# DIYTIL311_v0.net
KiCad netlist of a schematic drawn in EAGLE
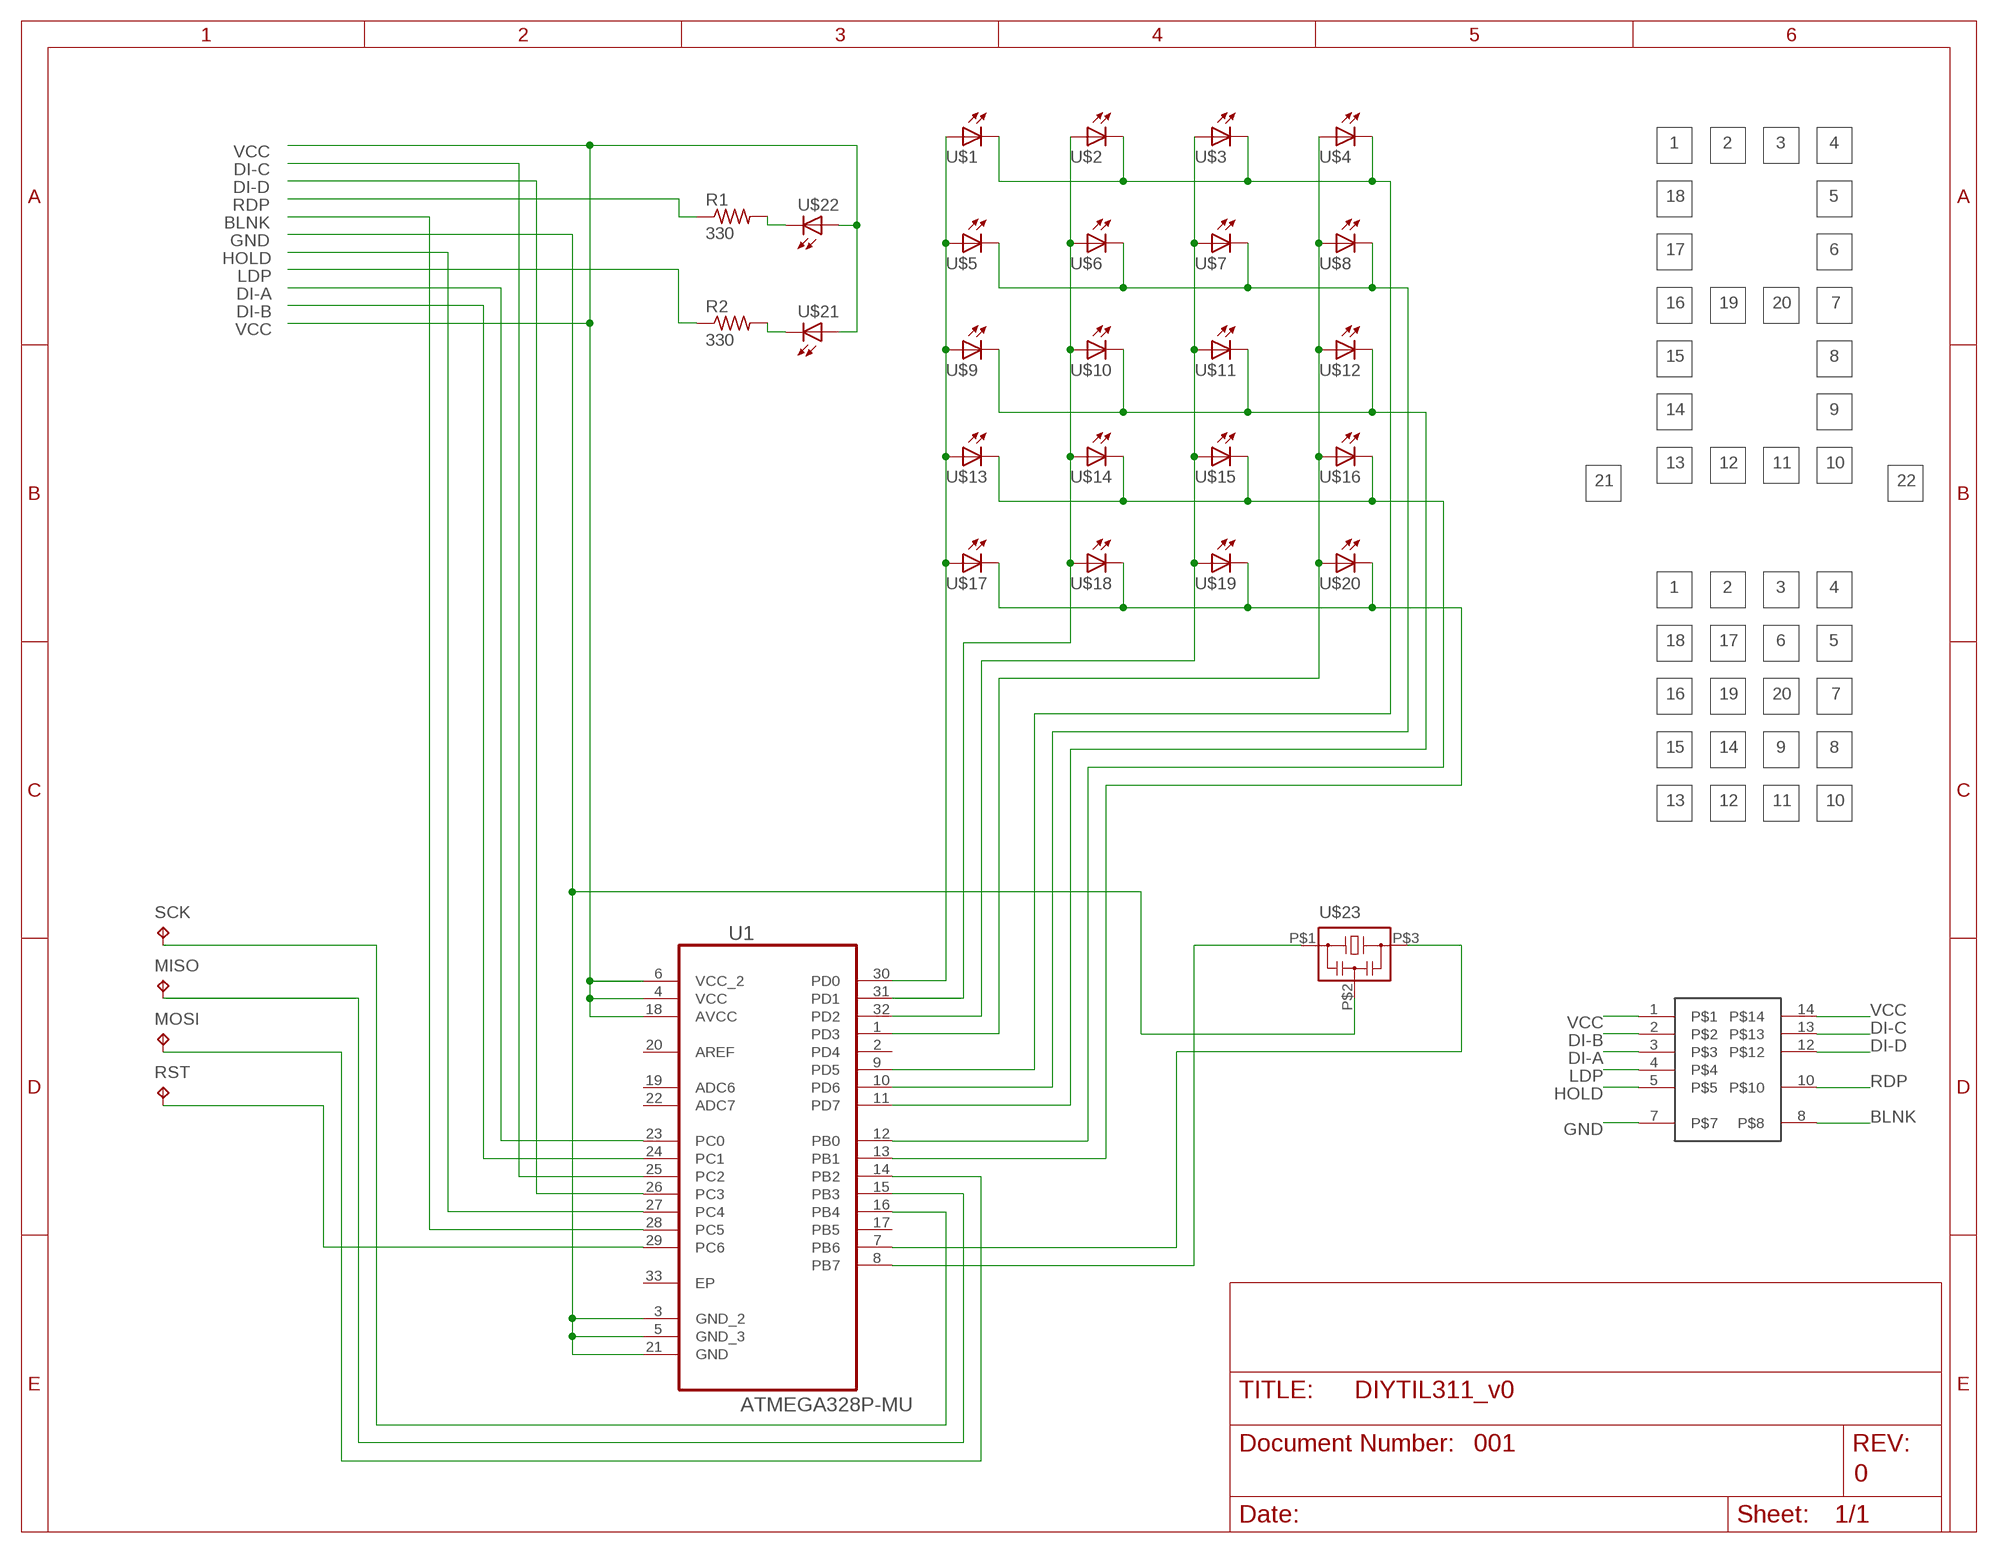
[diagram p0: schematic, sheet 1]

(export (version "E")
  (design (tool "Eeschema 10.0.6"))
  (components
    (comp (ref "MISO")
      (value "TPB1,27")
      (footprint "eagle-import:B1,27")
      (libsource (lib "eagle-import") (part "TPB1,27"))
    )
    (comp (ref "MOSI")
      (value "TPB1,27")
      (footprint "eagle-import:B1,27")
      (libsource (lib "eagle-import") (part "TPB1,27"))
    )
    (comp (ref "R1")
      (value "330")
      (footprint "eagle-import:R0201")
      (libsource (lib "eagle-import") (part "R-US_R0201"))
    )
    (comp (ref "R2")
      (value "330")
      (footprint "eagle-import:R0201")
      (libsource (lib "eagle-import") (part "R-US_R0201"))
    )
    (comp (ref "RST")
      (value "TPB1,27")
      (footprint "eagle-import:B1,27")
      (libsource (lib "eagle-import") (part "TPB1,27"))
    )
    (comp (ref "SCK")
      (value "TPB1,27")
      (footprint "eagle-import:B1,27")
      (libsource (lib "eagle-import") (part "TPB1,27"))
    )
    (comp (ref "U$1")
      (value "0201.LED0201")
      (footprint "eagle-import:LEDC0603X33")
      (libsource (lib "eagle-import") (part "0201.LED0201"))
    )
    (comp (ref "U$2")
      (value "0201.LED0201")
      (footprint "eagle-import:LEDC0603X33")
      (libsource (lib "eagle-import") (part "0201.LED0201"))
    )
    (comp (ref "U$3")
      (value "0201.LED0201")
      (footprint "eagle-import:LEDC0603X33")
      (libsource (lib "eagle-import") (part "0201.LED0201"))
    )
    (comp (ref "U$4")
      (value "0201.LED0201")
      (footprint "eagle-import:LEDC0603X33")
      (libsource (lib "eagle-import") (part "0201.LED0201"))
    )
    (comp (ref "U$5")
      (value "0201.LED0201")
      (footprint "eagle-import:LEDC0603X33")
      (libsource (lib "eagle-import") (part "0201.LED0201"))
    )
    (comp (ref "U$6")
      (value "0201.LED0201")
      (footprint "eagle-import:LEDC0603X33")
      (libsource (lib "eagle-import") (part "0201.LED0201"))
    )
    (comp (ref "U$7")
      (value "0201.LED0201")
      (footprint "eagle-import:LEDC0603X33")
      (libsource (lib "eagle-import") (part "0201.LED0201"))
    )
    (comp (ref "U$8")
      (value "0201.LED0201")
      (footprint "eagle-import:LEDC0603X33")
      (libsource (lib "eagle-import") (part "0201.LED0201"))
    )
    (comp (ref "U$9")
      (value "0201.LED0201")
      (footprint "eagle-import:LEDC0603X33")
      (libsource (lib "eagle-import") (part "0201.LED0201"))
    )
    (comp (ref "U$10")
      (value "0201.LED0201")
      (footprint "eagle-import:LEDC0603X33")
      (libsource (lib "eagle-import") (part "0201.LED0201"))
    )
    (comp (ref "U$11")
      (value "0201.LED0201")
      (footprint "eagle-import:LEDC0603X33")
      (libsource (lib "eagle-import") (part "0201.LED0201"))
    )
    (comp (ref "U$12")
      (value "0201.LED0201")
      (footprint "eagle-import:LEDC0603X33")
      (libsource (lib "eagle-import") (part "0201.LED0201"))
    )
    (comp (ref "U$13")
      (value "0201.LED0201")
      (footprint "eagle-import:LEDC0603X33")
      (libsource (lib "eagle-import") (part "0201.LED0201"))
    )
    (comp (ref "U$14")
      (value "0201.LED0201")
      (footprint "eagle-import:LEDC0603X33")
      (libsource (lib "eagle-import") (part "0201.LED0201"))
    )
    (comp (ref "U$15")
      (value "0201.LED0201")
      (footprint "eagle-import:LEDC0603X33")
      (libsource (lib "eagle-import") (part "0201.LED0201"))
    )
    (comp (ref "U$16")
      (value "0201.LED0201")
      (footprint "eagle-import:LEDC0603X33")
      (libsource (lib "eagle-import") (part "0201.LED0201"))
    )
    (comp (ref "U$17")
      (value "0201.LED0201")
      (footprint "eagle-import:LEDC0603X33")
      (libsource (lib "eagle-import") (part "0201.LED0201"))
    )
    (comp (ref "U$18")
      (value "0201.LED0201")
      (footprint "eagle-import:LEDC0603X33")
      (libsource (lib "eagle-import") (part "0201.LED0201"))
    )
    (comp (ref "U$19")
      (value "0201.LED0201")
      (footprint "eagle-import:LEDC0603X33")
      (libsource (lib "eagle-import") (part "0201.LED0201"))
    )
    (comp (ref "U$20")
      (value "0201.LED0201")
      (footprint "eagle-import:LEDC0603X33")
      (libsource (lib "eagle-import") (part "0201.LED0201"))
    )
    (comp (ref "U$21")
      (value "0201.LED0201")
      (footprint "eagle-import:LEDC0603X33")
      (libsource (lib "eagle-import") (part "0201.LED0201"))
    )
    (comp (ref "U$22")
      (value "0201.LED0201")
      (footprint "eagle-import:LEDC0603X33")
      (libsource (lib "eagle-import") (part "0201.LED0201"))
    )
    (comp (ref "U$23")
      (value "CSTNE16M0V53Z000R0")
      (footprint "eagle-import:MFF")
      (libsource (lib "eagle-import") (part "CSTNE16M0V53Z000R0"))
    )
    (comp (ref "U$24")
      (value "TIL311DIP")
      (footprint "eagle-import:TIL311DIP_FOOTPRINT")
      (libsource (lib "eagle-import") (part "TIL311DIP"))
    )
    (comp (ref "U1")
      (value "ATMEGA328P-MU")
      (footprint "eagle-import:QFN50P500X500X100-33N")
      (libsource (lib "eagle-import") (part "ATMEGA328P-MU"))
    )
  )
  (nets
    (net (code "1") (name "/BLNK") (class "Default")
      (node (ref "U$24") (pin "8") (pinfunction "P$8_8") (pintype "bidirectional"))
      (node (ref "U1") (pin "28") (pinfunction "PC5_28") (pintype "bidirectional"))
    )
    (net (code "2") (name "/DI-A") (class "Default")
      (node (ref "U$24") (pin "3") (pinfunction "P$3_3") (pintype "bidirectional"))
      (node (ref "U1") (pin "23") (pinfunction "PC0_23") (pintype "bidirectional"))
    )
    (net (code "3") (name "/DI-B") (class "Default")
      (node (ref "U$24") (pin "2") (pinfunction "P$2_2") (pintype "bidirectional"))
      (node (ref "U1") (pin "24") (pinfunction "PC1_24") (pintype "bidirectional"))
    )
    (net (code "4") (name "/DI-C") (class "Default")
      (node (ref "U$24") (pin "13") (pinfunction "P$13_13") (pintype "bidirectional"))
      (node (ref "U1") (pin "25") (pinfunction "PC2_25") (pintype "bidirectional"))
    )
    (net (code "5") (name "/DI-D") (class "Default")
      (node (ref "U$24") (pin "12") (pinfunction "P$12_12") (pintype "bidirectional"))
      (node (ref "U1") (pin "26") (pinfunction "PC3_26") (pintype "bidirectional"))
    )
    (net (code "6") (name "/GND") (class "Default")
      (node (ref "U$23") (pin "P$2") (pinfunction "2_P$2") (pintype "passive"))
      (node (ref "U$24") (pin "7") (pinfunction "P$7_7") (pintype "bidirectional"))
      (node (ref "U1") (pin "21") (pinfunction "GND_21") (pintype "passive"))
      (node (ref "U1") (pin "3") (pinfunction "GND_2_3") (pintype "passive"))
      (node (ref "U1") (pin "5") (pinfunction "GND_3_5") (pintype "passive"))
    )
    (net (code "7") (name "/HOLD") (class "Default")
      (node (ref "U$24") (pin "5") (pinfunction "P$5_5") (pintype "bidirectional"))
      (node (ref "U1") (pin "27") (pinfunction "PC4_27") (pintype "bidirectional"))
    )
    (net (code "8") (name "/LDP") (class "Default")
      (node (ref "R2") (pin "1") (pinfunction "1_1") (pintype "passive"))
      (node (ref "U$24") (pin "4") (pinfunction "P$4_4") (pintype "bidirectional"))
    )
    (net (code "9") (name "/RDP") (class "Default")
      (node (ref "R1") (pin "1") (pinfunction "1_1") (pintype "passive"))
      (node (ref "U$24") (pin "10") (pinfunction "P$10_10") (pintype "bidirectional"))
    )
    (net (code "10") (name "/VCC") (class "Default")
      (node (ref "U$21") (pin "1") (pinfunction "A_1") (pintype "passive"))
      (node (ref "U$22") (pin "1") (pinfunction "A_1") (pintype "passive"))
      (node (ref "U$24") (pin "1") (pinfunction "P$1_1") (pintype "bidirectional"))
      (node (ref "U$24") (pin "14") (pinfunction "P$14_14") (pintype "bidirectional"))
      (node (ref "U1") (pin "18") (pinfunction "AVCC_18") (pintype "power_in"))
      (node (ref "U1") (pin "4") (pinfunction "VCC_4") (pintype "power_in"))
      (node (ref "U1") (pin "6") (pinfunction "VCC_2_6") (pintype "power_in"))
    )
    (net (code "11") (name "Net-(U$1-A)") (class "Default")
      (node (ref "U$1") (pin "1") (pinfunction "A_1") (pintype "passive"))
      (node (ref "U$13") (pin "1") (pinfunction "A_1") (pintype "passive"))
      (node (ref "U$17") (pin "1") (pinfunction "A_1") (pintype "passive"))
      (node (ref "U$5") (pin "1") (pinfunction "A_1") (pintype "passive"))
      (node (ref "U$9") (pin "1") (pinfunction "A_1") (pintype "passive"))
      (node (ref "U1") (pin "30") (pinfunction "PD0_30") (pintype "bidirectional"))
    )
    (net (code "12") (name "Net-(U$1-C)") (class "Default")
      (node (ref "U$1") (pin "2") (pinfunction "C_2") (pintype "passive"))
      (node (ref "U$2") (pin "2") (pinfunction "C_2") (pintype "passive"))
      (node (ref "U$3") (pin "2") (pinfunction "C_2") (pintype "passive"))
      (node (ref "U$4") (pin "2") (pinfunction "C_2") (pintype "passive"))
      (node (ref "U1") (pin "9") (pinfunction "PD5_9") (pintype "bidirectional"))
    )
    (net (code "13") (name "Net-(U$5-C)") (class "Default")
      (node (ref "U$5") (pin "2") (pinfunction "C_2") (pintype "passive"))
      (node (ref "U$6") (pin "2") (pinfunction "C_2") (pintype "passive"))
      (node (ref "U$7") (pin "2") (pinfunction "C_2") (pintype "passive"))
      (node (ref "U$8") (pin "2") (pinfunction "C_2") (pintype "passive"))
      (node (ref "U1") (pin "10") (pinfunction "PD6_10") (pintype "bidirectional"))
    )
    (net (code "14") (name "Net-(U$10-A)") (class "Default")
      (node (ref "U$10") (pin "1") (pinfunction "A_1") (pintype "passive"))
      (node (ref "U$14") (pin "1") (pinfunction "A_1") (pintype "passive"))
      (node (ref "U$18") (pin "1") (pinfunction "A_1") (pintype "passive"))
      (node (ref "U$2") (pin "1") (pinfunction "A_1") (pintype "passive"))
      (node (ref "U$6") (pin "1") (pinfunction "A_1") (pintype "passive"))
      (node (ref "U1") (pin "31") (pinfunction "PD1_31") (pintype "bidirectional"))
    )
    (net (code "15") (name "Net-(U$10-C)") (class "Default")
      (node (ref "U$10") (pin "2") (pinfunction "C_2") (pintype "passive"))
      (node (ref "U$11") (pin "2") (pinfunction "C_2") (pintype "passive"))
      (node (ref "U$12") (pin "2") (pinfunction "C_2") (pintype "passive"))
      (node (ref "U$9") (pin "2") (pinfunction "C_2") (pintype "passive"))
      (node (ref "U1") (pin "11") (pinfunction "PD7_11") (pintype "bidirectional"))
    )
    (net (code "16") (name "Net-(U$11-A)") (class "Default")
      (node (ref "U$11") (pin "1") (pinfunction "A_1") (pintype "passive"))
      (node (ref "U$15") (pin "1") (pinfunction "A_1") (pintype "passive"))
      (node (ref "U$19") (pin "1") (pinfunction "A_1") (pintype "passive"))
      (node (ref "U$3") (pin "1") (pinfunction "A_1") (pintype "passive"))
      (node (ref "U$7") (pin "1") (pinfunction "A_1") (pintype "passive"))
      (node (ref "U1") (pin "32") (pinfunction "PD2_32") (pintype "bidirectional"))
    )
    (net (code "17") (name "Net-(U$12-A)") (class "Default")
      (node (ref "U$12") (pin "1") (pinfunction "A_1") (pintype "passive"))
      (node (ref "U$16") (pin "1") (pinfunction "A_1") (pintype "passive"))
      (node (ref "U$20") (pin "1") (pinfunction "A_1") (pintype "passive"))
      (node (ref "U$4") (pin "1") (pinfunction "A_1") (pintype "passive"))
      (node (ref "U$8") (pin "1") (pinfunction "A_1") (pintype "passive"))
      (node (ref "U1") (pin "1") (pinfunction "PD3_1") (pintype "bidirectional"))
    )
    (net (code "18") (name "Net-(U$13-C)") (class "Default")
      (node (ref "U$13") (pin "2") (pinfunction "C_2") (pintype "passive"))
      (node (ref "U$14") (pin "2") (pinfunction "C_2") (pintype "passive"))
      (node (ref "U$15") (pin "2") (pinfunction "C_2") (pintype "passive"))
      (node (ref "U$16") (pin "2") (pinfunction "C_2") (pintype "passive"))
      (node (ref "U1") (pin "12") (pinfunction "PB0_12") (pintype "bidirectional"))
    )
    (net (code "19") (name "Net-(U$17-C)") (class "Default")
      (node (ref "U$17") (pin "2") (pinfunction "C_2") (pintype "passive"))
      (node (ref "U$18") (pin "2") (pinfunction "C_2") (pintype "passive"))
      (node (ref "U$19") (pin "2") (pinfunction "C_2") (pintype "passive"))
      (node (ref "U$20") (pin "2") (pinfunction "C_2") (pintype "passive"))
      (node (ref "U1") (pin "13") (pinfunction "PB1_13") (pintype "bidirectional"))
    )
    (net (code "20") (name "Net-(U$21-C)") (class "Default")
      (node (ref "R2") (pin "2") (pinfunction "2_2") (pintype "passive"))
      (node (ref "U$21") (pin "2") (pinfunction "C_2") (pintype "passive"))
    )
    (net (code "21") (name "Net-(U$22-C)") (class "Default")
      (node (ref "R1") (pin "2") (pinfunction "2_2") (pintype "passive"))
      (node (ref "U$22") (pin "2") (pinfunction "C_2") (pintype "passive"))
    )
    (net (code "22") (name "Net-(U$23-1)") (class "Default")
      (node (ref "U$23") (pin "P$1") (pinfunction "1_P$1") (pintype "passive"))
      (node (ref "U1") (pin "8") (pinfunction "PB7_8") (pintype "bidirectional"))
    )
    (net (code "23") (name "Net-(U$23-3)") (class "Default")
      (node (ref "U$23") (pin "P$3") (pinfunction "3_P$3") (pintype "passive"))
      (node (ref "U1") (pin "7") (pinfunction "PB6_7") (pintype "bidirectional"))
    )
    (net (code "24") (name "Net-(U1-PB2)") (class "Default")
      (node (ref "MOSI") (pin "TP") (pinfunction "TP_TP") (pintype "input"))
      (node (ref "U1") (pin "14") (pinfunction "PB2_14") (pintype "bidirectional"))
    )
    (net (code "25") (name "Net-(U1-PB3)") (class "Default")
      (node (ref "MISO") (pin "TP") (pinfunction "TP_TP") (pintype "input"))
      (node (ref "U1") (pin "15") (pinfunction "PB3_15") (pintype "bidirectional"))
    )
    (net (code "26") (name "Net-(U1-PB4)") (class "Default")
      (node (ref "SCK") (pin "TP") (pinfunction "TP_TP") (pintype "input"))
      (node (ref "U1") (pin "16") (pinfunction "PB4_16") (pintype "bidirectional"))
    )
    (net (code "27") (name "Net-(U1-PC6)") (class "Default")
      (node (ref "RST") (pin "TP") (pinfunction "TP_TP") (pintype "input"))
      (node (ref "U1") (pin "29") (pinfunction "PC6_29") (pintype "bidirectional"))
    )
    (net (code "28") (name "unconnected-(U1-ADC6-Pad19)") (class "Default")
      (node (ref "U1") (pin "19") (pinfunction "ADC6_19") (pintype "input"))
    )
    (net (code "29") (name "unconnected-(U1-ADC7-Pad22)") (class "Default")
      (node (ref "U1") (pin "22") (pinfunction "ADC7_22") (pintype "input"))
    )
    (net (code "30") (name "unconnected-(U1-AREF-Pad20)") (class "Default")
      (node (ref "U1") (pin "20") (pinfunction "AREF_20") (pintype "input"))
    )
    (net (code "31") (name "unconnected-(U1-EP-Pad33)") (class "Default")
      (node (ref "U1") (pin "33") (pinfunction "EP_33") (pintype "passive"))
    )
    (net (code "32") (name "unconnected-(U1-PB5-Pad17)") (class "Default")
      (node (ref "U1") (pin "17") (pinfunction "PB5_17") (pintype "bidirectional"))
    )
    (net (code "33") (name "unconnected-(U1-PD4-Pad2)") (class "Default")
      (node (ref "U1") (pin "2") (pinfunction "PD4_2") (pintype "bidirectional"))
    )
  )
)
